# main.net
KiCad netlist of a schematic drawn in EAGLE
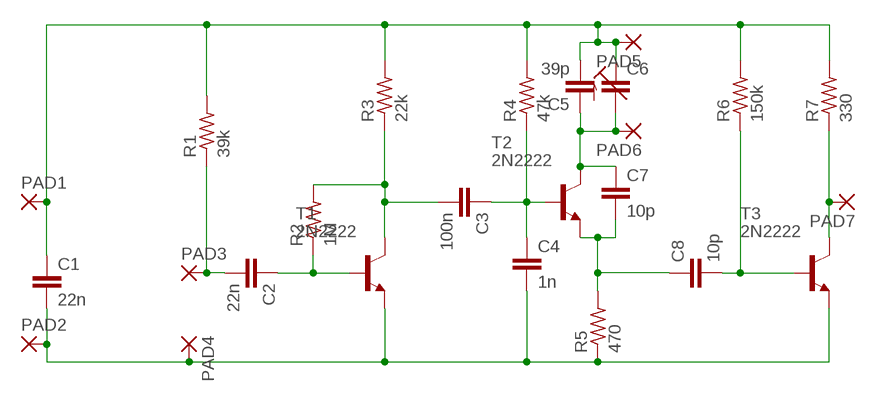
[diagram p0: schematic, sheet 1]

(export (version "E")
  (design (tool "Eeschema 10.0.6"))
  (components
    (comp (ref "C1")
      (value "22n")
      (footprint "eagle-import:C2.5-2")
      (libsource (lib "eagle-import") (part "C2.5/2"))
    )
    (comp (ref "C2")
      (value "22n")
      (footprint "eagle-import:C2.5-2")
      (libsource (lib "eagle-import") (part "C2.5/2"))
    )
    (comp (ref "C3")
      (value "100n")
      (footprint "eagle-import:C2.5-2")
      (libsource (lib "eagle-import") (part "C2.5/2"))
    )
    (comp (ref "C4")
      (value "1n")
      (footprint "eagle-import:C2.5-2")
      (libsource (lib "eagle-import") (part "C2.5/2"))
    )
    (comp (ref "C5")
      (value "39p")
      (footprint "eagle-import:C2.5-2")
      (libsource (lib "eagle-import") (part "C2.5/2"))
    )
    (comp (ref "C6")
      (value "C-TRIMM3050.504")
      (footprint "eagle-import:CTRIM3050.504")
      (libsource (lib "eagle-import") (part "C-TRIMM3050.504"))
    )
    (comp (ref "C7")
      (value "10p")
      (footprint "eagle-import:C2.5-2")
      (libsource (lib "eagle-import") (part "C2.5/2"))
    )
    (comp (ref "C8")
      (value "10p")
      (footprint "eagle-import:C2.5-2")
      (libsource (lib "eagle-import") (part "C2.5/2"))
    )
    (comp (ref "PAD1")
      (value "2,54/0,8")
      (footprint "eagle-import:2,54_0,8")
      (libsource (lib "eagle-import") (part "2,54/0,8"))
    )
    (comp (ref "PAD2")
      (value "2,54/0,8")
      (footprint "eagle-import:2,54_0,8")
      (libsource (lib "eagle-import") (part "2,54/0,8"))
    )
    (comp (ref "PAD3")
      (value "2,54/0,8")
      (footprint "eagle-import:2,54_0,8")
      (libsource (lib "eagle-import") (part "2,54/0,8"))
    )
    (comp (ref "PAD4")
      (value "2,54/0,8")
      (footprint "eagle-import:2,54_0,8")
      (libsource (lib "eagle-import") (part "2,54/0,8"))
    )
    (comp (ref "PAD5")
      (value "2,54/0,8")
      (footprint "eagle-import:2,54_0,8")
      (libsource (lib "eagle-import") (part "2,54/0,8"))
    )
    (comp (ref "PAD6")
      (value "2,54/0,8")
      (footprint "eagle-import:2,54_0,8")
      (libsource (lib "eagle-import") (part "2,54/0,8"))
    )
    (comp (ref "PAD7")
      (value "2,54/0,8")
      (footprint "eagle-import:2,54_0,8")
      (libsource (lib "eagle-import") (part "2,54/0,8"))
    )
    (comp (ref "R1")
      (value "39k")
      (footprint "eagle-import:0204V")
      (libsource (lib "eagle-import") (part "R-US_0204/2V"))
    )
    (comp (ref "R2")
      (value "1M")
      (footprint "eagle-import:0204V")
      (libsource (lib "eagle-import") (part "R-US_0204/2V"))
    )
    (comp (ref "R3")
      (value "22k")
      (footprint "eagle-import:0204V")
      (libsource (lib "eagle-import") (part "R-US_0204/2V"))
    )
    (comp (ref "R4")
      (value "47k")
      (footprint "eagle-import:0204V")
      (libsource (lib "eagle-import") (part "R-US_0204/2V"))
    )
    (comp (ref "R5")
      (value "470")
      (footprint "eagle-import:0204V")
      (libsource (lib "eagle-import") (part "R-US_0204/2V"))
    )
    (comp (ref "R6")
      (value "150k")
      (footprint "eagle-import:0204V")
      (libsource (lib "eagle-import") (part "R-US_0204/2V"))
    )
    (comp (ref "R7")
      (value "330")
      (footprint "eagle-import:0204V")
      (libsource (lib "eagle-import") (part "R-US_0204/2V"))
    )
    (comp (ref "T1")
      (value "2N2222")
      (footprint "eagle-import:TO92-EBC-OVAL")
      (libsource (lib "eagle-import") (part "2N2222"))
    )
    (comp (ref "T2")
      (value "2N2222")
      (footprint "eagle-import:TO92-EBC-OVAL")
      (libsource (lib "eagle-import") (part "2N2222"))
    )
    (comp (ref "T3")
      (value "2N2222")
      (footprint "eagle-import:TO92-EBC-OVAL")
      (libsource (lib "eagle-import") (part "2N2222"))
    )
  )
  (nets
    (net (code "1") (name "Net-(C2-Pad1)") (class "Default")
      (node (ref "C2") (pin "1") (pinfunction "1_1") (pintype "passive"))
      (node (ref "R2") (pin "1") (pinfunction "1_1") (pintype "passive"))
      (node (ref "T1") (pin "B") (pinfunction "B_B") (pintype "passive"))
    )
    (net (code "2") (name "Net-(C3-Pad1)") (class "Default")
      (node (ref "C3") (pin "1") (pinfunction "1_1") (pintype "passive"))
      (node (ref "C4") (pin "1") (pinfunction "1_1") (pintype "passive"))
      (node (ref "R4") (pin "1") (pinfunction "1_1") (pintype "passive"))
      (node (ref "T2") (pin "B") (pinfunction "B_B") (pintype "passive"))
    )
    (net (code "3") (name "Net-(C3-Pad2)") (class "Default")
      (node (ref "C3") (pin "2") (pinfunction "2_2") (pintype "passive"))
      (node (ref "R2") (pin "2") (pinfunction "2_2") (pintype "passive"))
      (node (ref "R3") (pin "1") (pinfunction "1_1") (pintype "passive"))
      (node (ref "T1") (pin "C") (pinfunction "C_C") (pintype "passive"))
    )
    (net (code "4") (name "Net-(C6-A)") (class "Default")
      (node (ref "C5") (pin "1") (pinfunction "1_1") (pintype "passive"))
      (node (ref "C6") (pin "2") (pinfunction "A_2") (pintype "passive"))
      (node (ref "C7") (pin "1") (pinfunction "1_1") (pintype "passive"))
      (node (ref "PAD6") (pin "1") (pinfunction "P_1") (pintype "passive"))
      (node (ref "T2") (pin "C") (pinfunction "C_C") (pintype "passive"))
    )
    (net (code "5") (name "Net-(C6-E)") (class "Default")
      (node (ref "C1") (pin "1") (pinfunction "1_1") (pintype "passive"))
      (node (ref "C5") (pin "2") (pinfunction "2_2") (pintype "passive"))
      (node (ref "C6") (pin "1") (pinfunction "E_1") (pintype "passive"))
      (node (ref "PAD1") (pin "1") (pinfunction "P_1") (pintype "passive"))
      (node (ref "PAD5") (pin "1") (pinfunction "P_1") (pintype "passive"))
      (node (ref "R1") (pin "2") (pinfunction "2_2") (pintype "passive"))
      (node (ref "R3") (pin "2") (pinfunction "2_2") (pintype "passive"))
      (node (ref "R4") (pin "2") (pinfunction "2_2") (pintype "passive"))
      (node (ref "R6") (pin "2") (pinfunction "2_2") (pintype "passive"))
      (node (ref "R7") (pin "2") (pinfunction "2_2") (pintype "passive"))
    )
    (net (code "6") (name "Net-(C7-Pad2)") (class "Default")
      (node (ref "C7") (pin "2") (pinfunction "2_2") (pintype "passive"))
      (node (ref "C8") (pin "1") (pinfunction "1_1") (pintype "passive"))
      (node (ref "R5") (pin "2") (pinfunction "2_2") (pintype "passive"))
      (node (ref "T2") (pin "E") (pinfunction "E_E") (pintype "passive"))
    )
    (net (code "7") (name "Net-(C8-Pad2)") (class "Default")
      (node (ref "C8") (pin "2") (pinfunction "2_2") (pintype "passive"))
      (node (ref "R6") (pin "1") (pinfunction "1_1") (pintype "passive"))
      (node (ref "T3") (pin "B") (pinfunction "B_B") (pintype "passive"))
    )
    (net (code "8") (name "Net-(PAD2-P)") (class "Default")
      (node (ref "C1") (pin "2") (pinfunction "2_2") (pintype "passive"))
      (node (ref "C4") (pin "2") (pinfunction "2_2") (pintype "passive"))
      (node (ref "PAD2") (pin "1") (pinfunction "P_1") (pintype "passive"))
      (node (ref "PAD4") (pin "1") (pinfunction "P_1") (pintype "passive"))
      (node (ref "R5") (pin "1") (pinfunction "1_1") (pintype "passive"))
      (node (ref "T1") (pin "E") (pinfunction "E_E") (pintype "passive"))
      (node (ref "T3") (pin "E") (pinfunction "E_E") (pintype "passive"))
    )
    (net (code "9") (name "Net-(PAD3-P)") (class "Default")
      (node (ref "C2") (pin "2") (pinfunction "2_2") (pintype "passive"))
      (node (ref "PAD3") (pin "1") (pinfunction "P_1") (pintype "passive"))
      (node (ref "R1") (pin "1") (pinfunction "1_1") (pintype "passive"))
    )
    (net (code "10") (name "Net-(PAD7-P)") (class "Default")
      (node (ref "PAD7") (pin "1") (pinfunction "P_1") (pintype "passive"))
      (node (ref "R7") (pin "1") (pinfunction "1_1") (pintype "passive"))
      (node (ref "T3") (pin "C") (pinfunction "C_C") (pintype "passive"))
    )
  )
)
